# MasterComm.net
KiCad netlist of a schematic drawn in Altium Designer
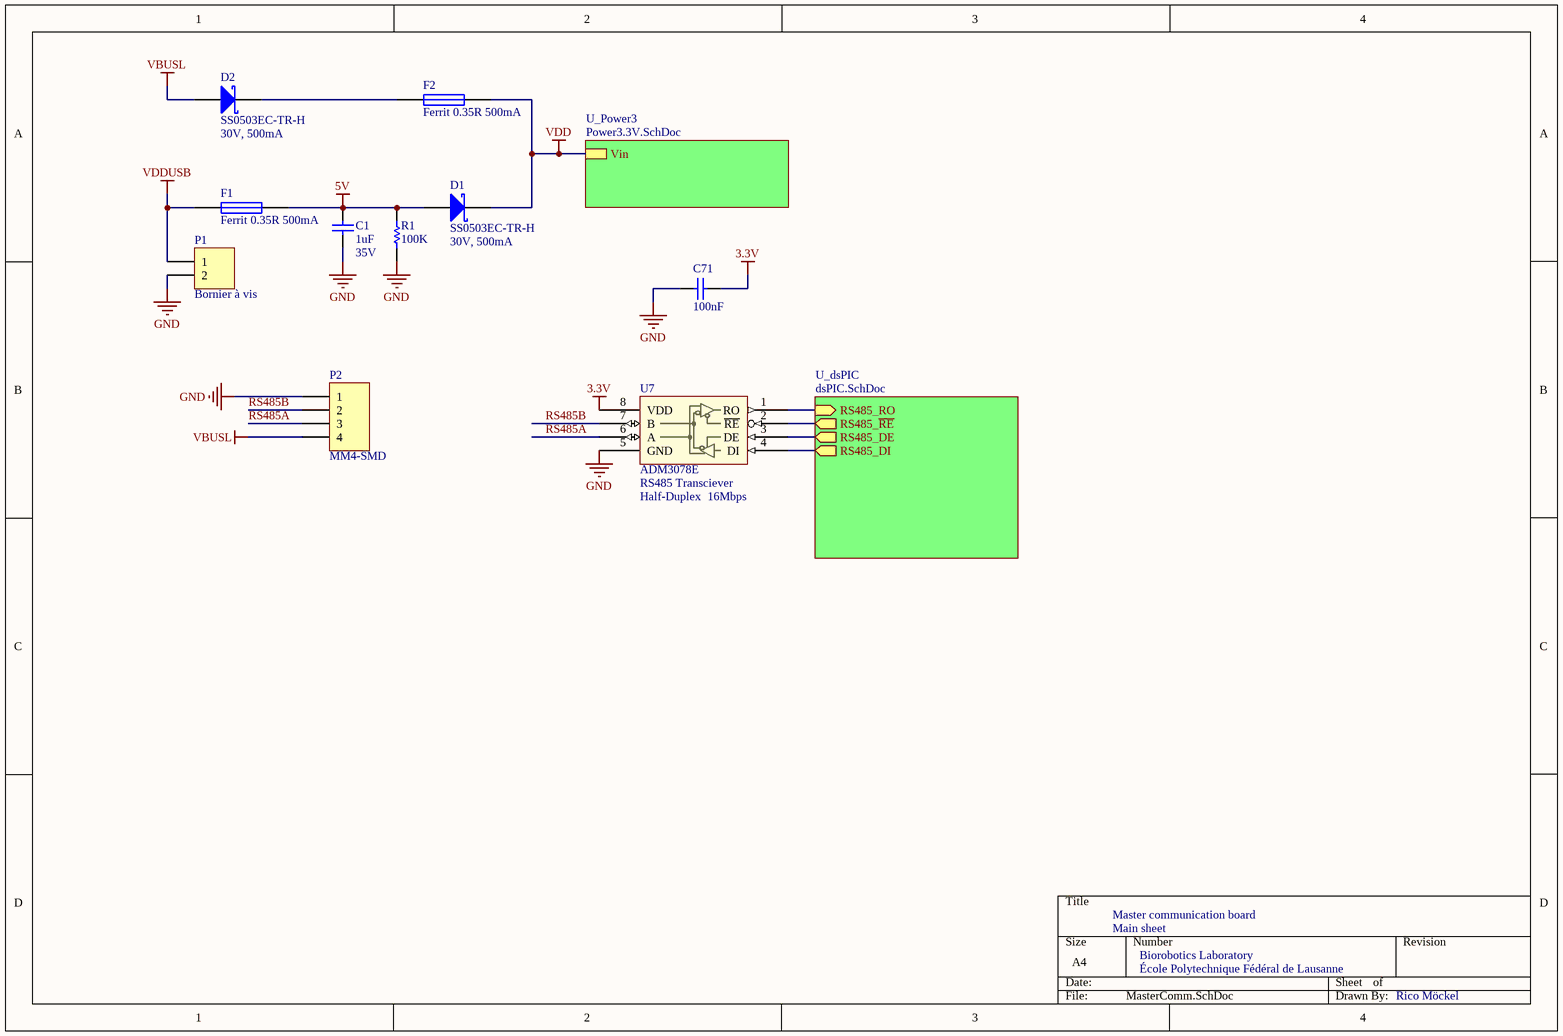
[diagram p0: MasterComm.SchDoc]

(export (version "E")
  (design (tool "Eeschema 10.0.6"))
  (components
    (comp (ref "C1")
      (value "1uF")
      (footprint "CAPC1608N")
      (description "Capacitor")
      (fields
        (field (name "VOLTAGE") "35V")
        (field (name "Comment") "1uF, 35V")
        (field (name "PUBLISHER") "Altium Limited")
      )
      (libsource (lib "Miscellaneous Devices") (part "Cap"))
    )
    (comp (ref "C71")
      (value "100nF")
      (footprint "CAPC1005N")
      (description "Capacitor")
      (fields (field (name "PUBLISHER") "Altium Limited"))
      (libsource (lib "Miscellaneous Devices") (part "Cap"))
    )
    (comp (ref "D1")
      (value "SS0503EC-TR-H")
      (footprint "RESC1005N")
      (description "Schottky Diode")
      (fields (field (name "VALUES") "30V, 500mA") (field (name "PUBLISHER") "Altium Limited"))
      (libsource (lib "Miscellaneous Devices") (part "D Schottky"))
    )
    (comp (ref "D2")
      (value "SS0503EC-TR-H")
      (footprint "RESC1005N")
      (description "Schottky Diode")
      (fields (field (name "VALUES") "30V, 500mA") (field (name "PUBLISHER") "Altium Limited"))
      (libsource (lib "Miscellaneous Devices") (part "D Schottky"))
    )
    (comp (ref "F1")
      (value "Ferrit 0.35R 500mA")
      (footprint "RESC1608N_R")
      (description "Ferrit Bead")
      (fields (field (name "PUBLISHER") "Altium Limited"))
      (libsource (lib "Miscellaneous Devices") (part "Fuse 1"))
    )
    (comp (ref "F2")
      (value "Ferrit 0.35R 500mA")
      (footprint "RESC1608N_R")
      (description "Ferrit Bead")
      (fields (field (name "PUBLISHER") "Altium Limited"))
      (libsource (lib "Miscellaneous Devices") (part "Fuse 1"))
    )
    (comp (ref "P1")
      (value "Bornier à vis")
      (description "Header, 2-Pin")
      (fields (field (name "PUBLISHER") "Altium Limited"))
      (libsource (lib "Miscellaneous Connectors") (part "Header 2"))
    )
    (comp (ref "P2")
      (value "MM4-SMD")
      (footprint "MM4-SMD")
      (description "Header, 4-Pin")
      (fields (field (name "PUBLISHER") "Altium Limited"))
      (libsource (lib "Miscellaneous Connectors") (part "Header 4"))
    )
    (comp (ref "R1")
      (value "100K")
      (footprint "RESC1005N")
      (description "Resistor")
      (fields (field (name "PUBLISHER") "Altium Limited"))
      (libsource (lib "Miscellaneous Devices") (part "Res1"))
    )
    (comp (ref "U7")
      (value "ADM3078E")
      (footprint "SOIC-8_M")
      (description "Half-Duplex RS485 Transciever, 3.3V, 16Mbps")
      (libsource (lib "Roombots") (part "ADM3078E"))
    )
  )
  (nets
    (net (code "1") (name "/RS485A") (class "Default")
      (node (ref "P2") (pin "3") (pinfunction "3_3") (pintype "passive"))
      (node (ref "U7") (pin "6") (pinfunction "A_6") (pintype "bidirectional"))
    )
    (net (code "2") (name "/RS485B") (class "Default")
      (node (ref "P2") (pin "2") (pinfunction "2_2") (pintype "passive"))
      (node (ref "U7") (pin "7") (pinfunction "B_7") (pintype "bidirectional"))
    )
    (net (code "3") (name "/RS485_DE") (class "Default")
      (node (ref "U7") (pin "3") (pinfunction "DE_3") (pintype "input"))
    )
    (net (code "4") (name "/RS485_DI") (class "Default")
      (node (ref "U7") (pin "4") (pinfunction "DI_4") (pintype "input"))
    )
    (net (code "5") (name "/RS485_RO") (class "Default")
      (node (ref "U7") (pin "1") (pinfunction "RO_1") (pintype "output"))
    )
    (net (code "6") (name "/RS485_~{RE}") (class "Default")
      (node (ref "U7") (pin "2") (pinfunction "~{RE}_2") (pintype "input"))
    )
    (net (code "7") (name "3.3V") (class "Default")
      (node (ref "C71") (pin "1") (pinfunction "1_1") (pintype "passive"))
      (node (ref "U7") (pin "8") (pinfunction "VDD_8") (pintype "power_in"))
    )
    (net (code "8") (name "5V") (class "Default")
      (node (ref "C1") (pin "2") (pinfunction "2_2") (pintype "passive"))
      (node (ref "D1") (pin "1") (pinfunction "A_1") (pintype "passive"))
      (node (ref "F1") (pin "2") (pinfunction "2_2") (pintype "passive"))
      (node (ref "R1") (pin "1") (pinfunction "1_1") (pintype "passive"))
    )
    (net (code "9") (name "GND") (class "Default")
      (node (ref "C1") (pin "1") (pinfunction "1_1") (pintype "passive"))
      (node (ref "C71") (pin "2") (pinfunction "2_2") (pintype "passive"))
      (node (ref "P1") (pin "2") (pinfunction "2_2") (pintype "passive"))
      (node (ref "P2") (pin "1") (pinfunction "1_1") (pintype "passive"))
      (node (ref "R1") (pin "2") (pinfunction "2_2") (pintype "passive"))
      (node (ref "U7") (pin "5") (pinfunction "GND_5") (pintype "power_in"))
    )
    (net (code "10") (name "Net-(D2-K)") (class "Default")
      (node (ref "D2") (pin "2") (pinfunction "K_2") (pintype "passive"))
      (node (ref "F2") (pin "1") (pinfunction "1_1") (pintype "passive"))
    )
    (net (code "11") (name "VBUSL") (class "Default")
      (node (ref "D2") (pin "1") (pinfunction "A_1") (pintype "passive"))
      (node (ref "P2") (pin "4") (pinfunction "4_4") (pintype "passive"))
    )
    (net (code "12") (name "VDD") (class "Default")
      (node (ref "D1") (pin "2") (pinfunction "K_2") (pintype "passive"))
      (node (ref "F2") (pin "2") (pinfunction "2_2") (pintype "passive"))
    )
    (net (code "13") (name "VDDUSB") (class "Default")
      (node (ref "F1") (pin "1") (pinfunction "1_1") (pintype "passive"))
      (node (ref "P1") (pin "1") (pinfunction "1_1") (pintype "passive"))
    )
  )
)
